# Sheet3.net
KiCad netlist of a schematic drawn in Altium Designer
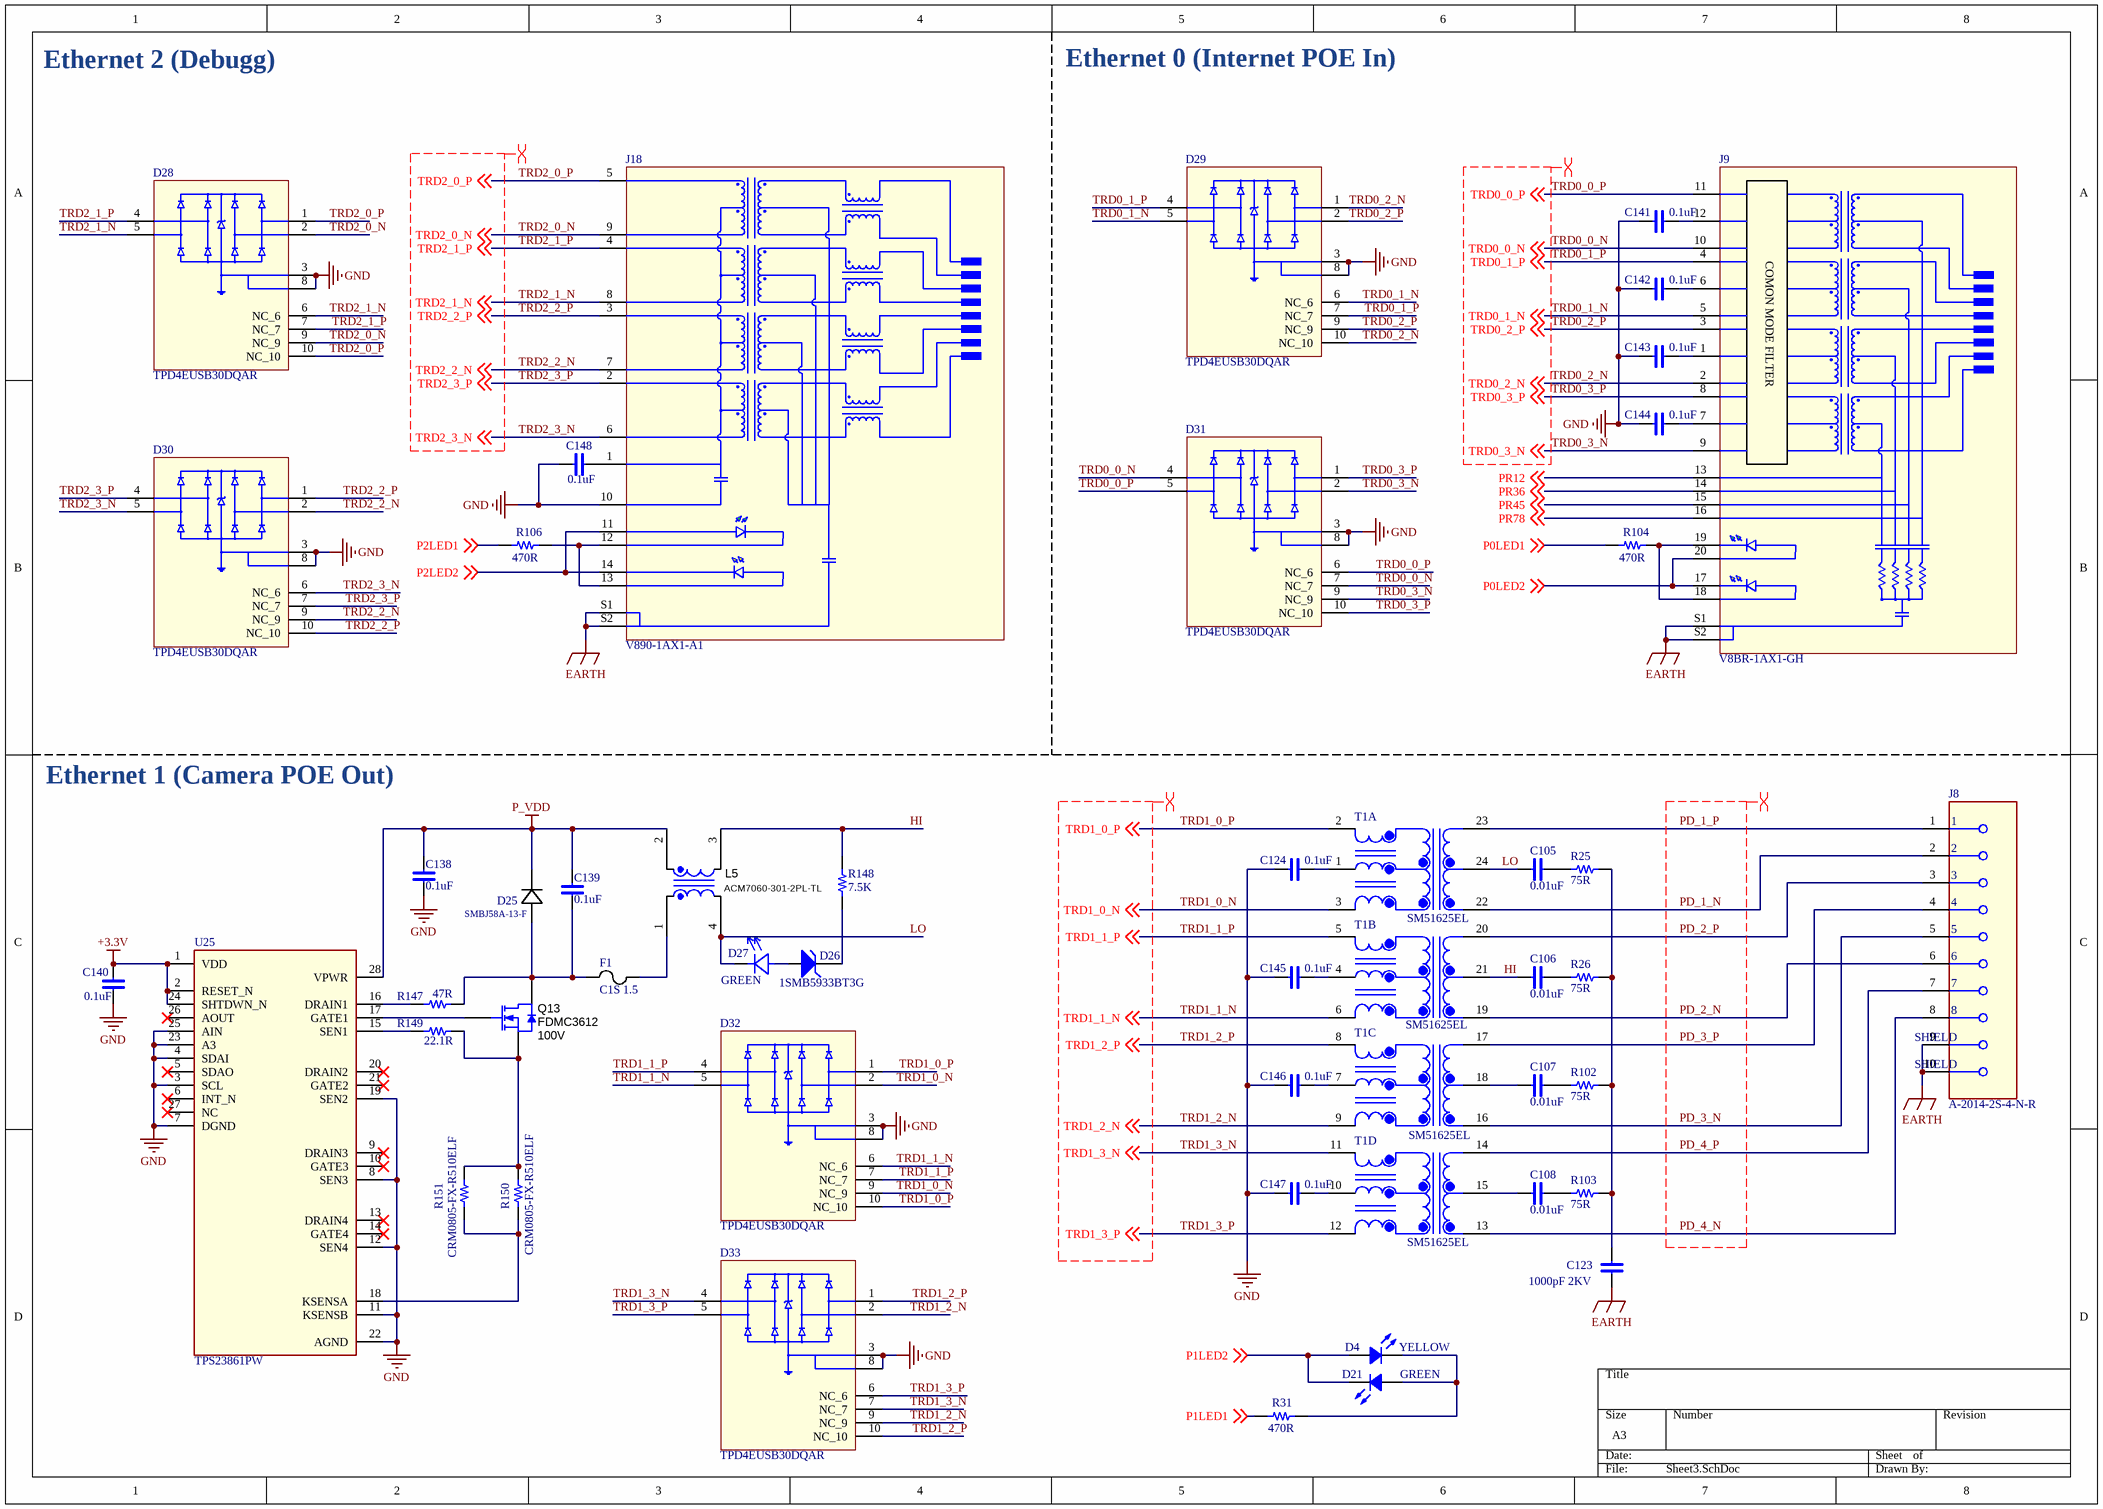
[diagram p0: Sheet3.SchDoc]

(export (version "E")
  (design (tool "Eeschema 10.0.6"))
  (components
    (comp (ref "C105")
      (value "0.01uF")
      (footprint "C-0402/1005")
      (description "CAP CER 0.1UF 50V X7R 0402")
      (fields (field (name "MFR. PART NO.") "UMK105B7104KV-FR"))
      (libsource (lib "") (part "Capacitor-NonPolar_3"))
    )
    (comp (ref "C106")
      (value "0.01uF")
      (footprint "C-0402/1005")
      (description "CAP CER 0.1UF 50V X7R 0402")
      (fields (field (name "MFR. PART NO.") "UMK105B7104KV-FR"))
      (libsource (lib "") (part "Capacitor-NonPolar_3"))
    )
    (comp (ref "C107")
      (value "0.01uF")
      (footprint "C-0402/1005")
      (description "CAP CER 0.1UF 50V X7R 0402")
      (fields (field (name "MFR. PART NO.") "UMK105B7104KV-FR"))
      (libsource (lib "") (part "Capacitor-NonPolar_3"))
    )
    (comp (ref "C108")
      (value "0.01uF")
      (footprint "C-0402/1005")
      (description "CAP CER 0.1UF 50V X7R 0402")
      (fields (field (name "MFR. PART NO.") "UMK105B7104KV-FR"))
      (libsource (lib "") (part "Capacitor-NonPolar_3"))
    )
    (comp (ref "C123")
      (value "1000pF 2KV")
      (footprint "C-0402/1005")
      (description "CAP CER 0.1UF 50V X7R 0402")
      (fields (field (name "MFR. PART NO.") "UMK105B7104KV-FR"))
      (libsource (lib "") (part "Capacitor-NonPolar_2"))
    )
    (comp (ref "C124")
      (value "0.1uF")
      (footprint "C-0402/1005")
      (description "CAP CER 0.1UF 50V X7R 0402")
      (fields (field (name "MFR. PART NO.") "UMK105B7104KV-FR"))
      (libsource (lib "") (part "Capacitor-NonPolar_1"))
    )
    (comp (ref "C138")
      (value "0.1uF")
      (footprint "C-0402/1005")
      (description "CAP CER 0.1UF 50V X7R 0402")
      (fields (field (name "MFR. PART NO.") "UMK105B7104KV-FR"))
      (libsource (lib "Custom_Library") (part "Capacitor-NonPolar"))
    )
    (comp (ref "C139")
      (value "0.1uF")
      (footprint "C-0402/1005")
      (description "CAP CER 0.1UF 50V X7R 0402")
      (fields (field (name "MFR. PART NO.") "UMK105B7104KV-FR"))
      (libsource (lib "Custom_Library") (part "Capacitor-NonPolar"))
    )
    (comp (ref "C140")
      (value "0.1uF")
      (footprint "C-0402/1005")
      (description "CAP CER 0.1UF 50V X7R 0402")
      (fields (field (name "MFR. PART NO.") "UMK105B7104KV-FR"))
      (libsource (lib "Custom_Library") (part "Capacitor-NonPolar"))
    )
    (comp (ref "C141")
      (value "0.1uF")
      (footprint "C-0402/1005")
      (description "CAP CER 0.1UF 50V X7R 0402")
      (fields (field (name "MFR. PART NO.") "UMK105B7104KV-FR"))
      (libsource (lib "") (part "Capacitor-NonPolar_1"))
    )
    (comp (ref "C142")
      (value "0.1uF")
      (footprint "C-0402/1005")
      (description "CAP CER 0.1UF 50V X7R 0402")
      (fields (field (name "MFR. PART NO.") "UMK105B7104KV-FR"))
      (libsource (lib "") (part "Capacitor-NonPolar_1"))
    )
    (comp (ref "C143")
      (value "0.1uF")
      (footprint "C-0402/1005")
      (description "CAP CER 0.1UF 50V X7R 0402")
      (fields (field (name "MFR. PART NO.") "UMK105B7104KV-FR"))
      (libsource (lib "") (part "Capacitor-NonPolar_1"))
    )
    (comp (ref "C144")
      (value "0.1uF")
      (footprint "C-0402/1005")
      (description "CAP CER 0.1UF 50V X7R 0402")
      (fields (field (name "MFR. PART NO.") "UMK105B7104KV-FR"))
      (libsource (lib "") (part "Capacitor-NonPolar_1"))
    )
    (comp (ref "C145")
      (value "0.1uF")
      (footprint "C-0402/1005")
      (description "CAP CER 0.1UF 50V X7R 0402")
      (fields (field (name "MFR. PART NO.") "UMK105B7104KV-FR"))
      (libsource (lib "") (part "Capacitor-NonPolar_1"))
    )
    (comp (ref "C146")
      (value "0.1uF")
      (footprint "C-0402/1005")
      (description "CAP CER 0.1UF 50V X7R 0402")
      (fields (field (name "MFR. PART NO.") "UMK105B7104KV-FR"))
      (libsource (lib "") (part "Capacitor-NonPolar_1"))
    )
    (comp (ref "C147")
      (value "0.1uF")
      (footprint "C-0402/1005")
      (description "CAP CER 0.1UF 50V X7R 0402")
      (fields (field (name "MFR. PART NO.") "UMK105B7104KV-FR"))
      (libsource (lib "") (part "Capacitor-NonPolar_1"))
    )
    (comp (ref "C148")
      (value "0.1uF")
      (footprint "C-0402/1005")
      (description "CAP CER 0.1UF 50V X7R 0402")
      (fields (field (name "MFR. PART NO.") "UMK105B7104KV-FR"))
      (libsource (lib "") (part "Capacitor-NonPolar_1"))
    )
    (comp (ref "D4")
      (value "YELLOW")
      (footprint "LED-0603-RED")
      (description "LED RED CLEAR CHIP SMD R/A")
      (fields (field (name "MFR. PART NO.") "LTST-S270KRKT"))
      (libsource (lib "Diodes") (part "LED SMD"))
    )
    (comp (ref "D21")
      (value "GREEN")
      (footprint "LED-0603-RED")
      (description "LED RED CLEAR CHIP SMD R/A")
      (fields (field (name "MFR. PART NO.") "LTST-S270KRKT"))
      (libsource (lib "Diodes") (part "LED SMD"))
    )
    (comp (ref "D25")
      (value "SMBJ58A-13-F")
      (footprint "CR_SM12CA-13-F_DIO")
      (description "No Description Available")
      (fields (field (name "COPYRIGHT") "Copyright (C) 2023 Ultra Librarian. All rights reserved."))
      (libsource (lib "SMBJ58A-13-F") (part "SMBJ58A-13-F"))
    )
    (comp (ref "D26")
      (value "1SMB5933BT3G")
      (footprint "ONSC-SMB-2-403A-03_H_V")
      (description "3 W Zener Voltage Regulator, 2-Pin SMB, Pb-Free, Tape and Reel")
      (fields (field (name "MANUFACTURER") "On Semiconductor"))
      (libsource (lib "Altium Content Vault") (part "ONSC-K1A2-2"))
    )
    (comp (ref "D27")
      (value "GREEN")
      (footprint "LED-0603-Green")
      (libsource (lib "Custom_Library") (part "Diode-LED"))
    )
    (comp (ref "D28")
      (value "TPD4EUSB30DQAR")
      (footprint "IC_TPD4EUSB30DQAR")
      (description "4-channel ESD solution for SuperSpeed (6 Gbps) USB 3.0 interface 10-USON -40 to 85")
      (libsource (lib "TPD4EUSB30DQAR") (part "TPD4EUSB30DQAR"))
    )
    (comp (ref "D29")
      (value "TPD4EUSB30DQAR")
      (footprint "IC_TPD4EUSB30DQAR")
      (description "4-channel ESD solution for SuperSpeed (6 Gbps) USB 3.0 interface 10-USON -40 to 85")
      (libsource (lib "TPD4EUSB30DQAR") (part "TPD4EUSB30DQAR"))
    )
    (comp (ref "D30")
      (value "TPD4EUSB30DQAR")
      (footprint "IC_TPD4EUSB30DQAR")
      (description "4-channel ESD solution for SuperSpeed (6 Gbps) USB 3.0 interface 10-USON -40 to 85")
      (libsource (lib "TPD4EUSB30DQAR") (part "TPD4EUSB30DQAR"))
    )
    (comp (ref "D31")
      (value "TPD4EUSB30DQAR")
      (footprint "IC_TPD4EUSB30DQAR")
      (description "4-channel ESD solution for SuperSpeed (6 Gbps) USB 3.0 interface 10-USON -40 to 85")
      (libsource (lib "TPD4EUSB30DQAR") (part "TPD4EUSB30DQAR"))
    )
    (comp (ref "D32")
      (value "TPD4EUSB30DQAR")
      (footprint "IC_TPD4EUSB30DQAR")
      (description "4-channel ESD solution for SuperSpeed (6 Gbps) USB 3.0 interface 10-USON -40 to 85")
      (libsource (lib "TPD4EUSB30DQAR") (part "TPD4EUSB30DQAR"))
    )
    (comp (ref "D33")
      (value "TPD4EUSB30DQAR")
      (footprint "IC_TPD4EUSB30DQAR")
      (description "4-channel ESD solution for SuperSpeed (6 Gbps) USB 3.0 interface 10-USON -40 to 85")
      (libsource (lib "TPD4EUSB30DQAR") (part "TPD4EUSB30DQAR"))
    )
    (comp (ref "F1")
      (value "C1S 1.5")
      (footprint "C1_BEL")
      (description "No Description Available")
      (fields (field (name "COPYRIGHT") "Copyright (C) 2023 Ultra Librarian. All rights reserved."))
      (libsource (lib "C1S1P5") (part "C1S 1.5"))
    )
    (comp (ref "J8")
      (value "A-2014-2S-4-N-R")
      (footprint "ASSMANN_A-2014-2S-4-N-R")
      (description "Jack Modular Connector 8p8c (RJ45, Ethernet) Vertical Unshielded")
      (fields (field (name "MP") "A-2014-2-4-N-T-R") (field (name "MF") "ASSMANN WSW Components"))
      (libsource (lib "A-2014-2-4-N-T-R") (part "A-2014-2-4-N-T-R"))
    )
    (comp (ref "J9")
      (value "V8BR-1AX1-GH")
      (footprint "V8BR1AX1GH")
      (description "Conn RJ-45 F 8 POS 1.02mm Solder ST Thru-Hole 20 Terminal 1 Port Tray")
      (fields (field (name "MOUSER PART NUMBER") "530-V8BR-1AX1-GH"))
      (libsource (lib "V8BR-1AX1-GH") (part "V8BR-1AX1-GH"))
    )
    (comp (ref "J18")
      (value "V890-1AX1-A1")
      (footprint "BEL_V890-1AX1-A1")
      (description "MagJack 1000BaseT ¦ 1X1 ¦ G/Y ¦ Vertical ¦ RoHS")
      (fields
        (field (name "MF") "Bel Magnetic Solutions")
        (field (name "DIGI-KEY_PART_NUMBER") "V890-1AX1-A1A-ND")
      )
      (libsource (lib "V890-1AX1-A1") (part "V890-1AX1-A1"))
    )
    (comp (ref "L5")
      (value "ACM7060-301-2PL-TL")
      (footprint "IND_ACM7060_TDK")
      (description "Coupled inductor, 5A, 0.01 ohm, SMD")
      (fields
        (field (name "MANUFACTURER") "TDK")
        (field (name "SYMBOLCREATOR") "a0799628")
        (field (name "PUBLISHER") "Texas Instruments")
      )
      (libsource (lib "Coupled_Inductors") (part "ACM7060-301-2PL-TL"))
    )
    (comp (ref "Q13")
      (value "FDMC3612")
      (footprint "MLP8_3P3X3P3_ONS")
      (description "MOSFET, N-CH, 100V, 3.3A, 3.3x1x3.3mm")
      (fields
        (field (name "MANUFACTURER") "Fairchild Semiconductor")
        (field (name "ALTIUM_VALUE") "100V")
        (field (name "PUBLISHER") "Texas Instruments")
      )
      (libsource (lib "PC22") (part "FDMC3612"))
    )
    (comp (ref "R25")
      (value "75R")
      (footprint "R-0402/1005")
      (description "RES SMD 51 OHM 0.5% 1/16W 0402")
      (fields (field (name "MFR. PART NO.") "ERA-2AED510X"))
      (libsource (lib "Custom_Library") (part "Resistor"))
    )
    (comp (ref "R26")
      (value "75R")
      (footprint "R-0402/1005")
      (description "RES SMD 51 OHM 0.5% 1/16W 0402")
      (fields (field (name "MFR. PART NO.") "ERA-2AED510X"))
      (libsource (lib "Custom_Library") (part "Resistor"))
    )
    (comp (ref "R31")
      (value "470R")
      (footprint "R-0402/1005")
      (description "RES SMD 51 OHM 0.5% 1/16W 0402")
      (fields (field (name "MFR. PART NO.") "ERA-2AED510X"))
      (libsource (lib "Custom_Library") (part "Resistor"))
    )
    (comp (ref "R102")
      (value "75R")
      (footprint "R-0402/1005")
      (description "RES SMD 51 OHM 0.5% 1/16W 0402")
      (fields (field (name "MFR. PART NO.") "ERA-2AED510X"))
      (libsource (lib "Custom_Library") (part "Resistor"))
    )
    (comp (ref "R103")
      (value "75R")
      (footprint "R-0402/1005")
      (description "RES SMD 51 OHM 0.5% 1/16W 0402")
      (fields (field (name "MFR. PART NO.") "ERA-2AED510X"))
      (libsource (lib "Custom_Library") (part "Resistor"))
    )
    (comp (ref "R104")
      (value "470R")
      (footprint "R-0402/1005")
      (description "RES SMD 51 OHM 0.5% 1/16W 0402")
      (fields (field (name "MFR. PART NO.") "ERA-2AED510X"))
      (libsource (lib "Custom_Library") (part "Resistor"))
    )
    (comp (ref "R106")
      (value "470R")
      (footprint "R-0402/1005")
      (description "RES SMD 51 OHM 0.5% 1/16W 0402")
      (fields (field (name "MFR. PART NO.") "ERA-2AED510X"))
      (libsource (lib "Custom_Library") (part "Resistor"))
    )
    (comp (ref "R147")
      (value "47R")
      (footprint "R-0402/1005")
      (description "RES SMD 51 OHM 0.5% 1/16W 0402")
      (fields (field (name "MFR. PART NO.") "ERA-2AED510X"))
      (libsource (lib "Custom_Library") (part "Resistor"))
    )
    (comp (ref "R148")
      (value "7.5K")
      (footprint "R-0805/2012")
      (description "RES SMD 51 OHM 0.5% 1/16W 0402")
      (fields (field (name "MFR. PART NO.") "ERA-2AED510X"))
      (libsource (lib "Custom_Library") (part "Resistor"))
    )
    (comp (ref "R149")
      (value "22.1R")
      (footprint "R-0402/1005")
      (description "RES SMD 51 OHM 0.5% 1/16W 0402")
      (fields (field (name "MFR. PART NO.") "ERA-2AED510X"))
      (libsource (lib "Custom_Library") (part "Resistor"))
    )
    (comp (ref "R150")
      (value "CRM0805-FX-R510ELF")
      (footprint "R-0805/2012")
      (description "RES SMD 51 OHM 0.5% 1/16W 0402")
      (fields (field (name "MFR. PART NO.") "ERA-2AED510X"))
      (libsource (lib "Custom_Library") (part "Resistor"))
    )
    (comp (ref "R151")
      (value "CRM0805-FX-R510ELF")
      (footprint "R-0805/2012")
      (description "RES SMD 51 OHM 0.5% 1/16W 0402")
      (fields (field (name "MFR. PART NO.") "ERA-2AED510X"))
      (libsource (lib "Custom_Library") (part "Resistor"))
    )
    (comp (ref "T1")
      (value "SM51625EL")
      (footprint "XFMR_SM51625EL")
      (description "350ÂµH LAN 10/100/1000 Base-T Pulse Transformer 1CT:1CT Transmitter, 1CT:1CT Receiver Surface Mount")
      (fields (field (name "MF") "Wurth Electronics") (field (name "MP") "7490220122"))
      (libsource (lib "7490220122") (part "7490220122"))
    )
    (comp (ref "U25")
      (value "TPS23861PW")
      (footprint "PW0028A_N")
      (description "No Description Available")
      (fields (field (name "COPYRIGHT") "Copyright (C) 2023 Ultra Librarian. All rights reserved."))
      (libsource (lib "TPS23861PW") (part "TPS23861PW"))
    )
  )
  (nets
    (net (code "1") (name "+3.3V") (class "Default")
      (node (ref "C140") (pin "1") (pinfunction "1_1") (pintype "passive"))
      (node (ref "U25") (pin "1") (pinfunction "VDD_1") (pintype "passive"))
      (node (ref "U25") (pin "2") (pinfunction "RESET_N_2") (pintype "passive"))
      (node (ref "U25") (pin "24") (pinfunction "SHTDWN_N_24") (pintype "passive"))
    )
    (net (code "2") (name "/HI") (class "Default")
      (node (ref "C106") (pin "1") (pinfunction "1_1") (pintype "passive"))
      (node (ref "L5") (pin "3") (pinfunction "3_3") (pintype "passive"))
      (node (ref "R148") (pin "2") (pinfunction "2_2") (pintype "passive"))
      (node (ref "T1") (pin "21") (pinfunction "MCT2_21") (pintype "passive"))
    )
    (net (code "3") (name "/LO") (class "Default")
      (node (ref "C105") (pin "1") (pinfunction "1_1") (pintype "passive"))
      (node (ref "D27") (pin "2") (pinfunction "2_2") (pintype "passive"))
      (node (ref "L5") (pin "4") (pinfunction "4_4") (pintype "passive"))
      (node (ref "T1") (pin "24") (pinfunction "MCT1_24") (pintype "passive"))
    )
    (net (code "4") (name "/PD_1_N") (class "Default")
      (node (ref "J8") (pin "2") (pinfunction "2_2") (pintype "passive"))
      (node (ref "T1") (pin "22") (pinfunction "MX1-_22") (pintype "passive"))
    )
    (net (code "5") (name "/PD_1_P") (class "Default")
      (node (ref "J8") (pin "1") (pinfunction "1_1") (pintype "passive"))
      (node (ref "T1") (pin "23") (pinfunction "MX1+_23") (pintype "passive"))
    )
    (net (code "6") (name "/PD_2_N") (class "Default")
      (node (ref "J8") (pin "6") (pinfunction "6_6") (pintype "passive"))
      (node (ref "T1") (pin "19") (pinfunction "MX2-_19") (pintype "passive"))
    )
    (net (code "7") (name "/PD_2_P") (class "Default")
      (node (ref "J8") (pin "3") (pinfunction "3_3") (pintype "passive"))
      (node (ref "T1") (pin "20") (pinfunction "MX2+_20") (pintype "passive"))
    )
    (net (code "8") (name "/PD_3_N") (class "Default")
      (node (ref "J8") (pin "5") (pinfunction "5_5") (pintype "passive"))
      (node (ref "T1") (pin "16") (pinfunction "MX3-_16") (pintype "passive"))
    )
    (net (code "9") (name "/PD_3_P") (class "Default")
      (node (ref "J8") (pin "4") (pinfunction "4_4") (pintype "passive"))
      (node (ref "T1") (pin "17") (pinfunction "MX3+_17") (pintype "passive"))
    )
    (net (code "10") (name "/PD_4_N") (class "Default")
      (node (ref "J8") (pin "8") (pinfunction "8_8") (pintype "passive"))
      (node (ref "T1") (pin "13") (pinfunction "MX4-_13") (pintype "passive"))
    )
    (net (code "11") (name "/PD_4_P") (class "Default")
      (node (ref "J8") (pin "7") (pinfunction "7_7") (pintype "passive"))
      (node (ref "T1") (pin "14") (pinfunction "MX4+_14") (pintype "passive"))
    )
    (net (code "12") (name "EARTH") (class "Default")
      (node (ref "C123") (pin "2") (pinfunction "2_2") (pintype "passive"))
      (node (ref "J18") (pin "S1") (pinfunction "SHIELD_S1") (pintype "passive"))
      (node (ref "J18") (pin "S2") (pinfunction "SHIELD_S2") (pintype "passive"))
      (node (ref "J8") (pin "10") (pinfunction "MNT_2_10") (pintype "passive"))
      (node (ref "J8") (pin "9") (pinfunction "MNT_1_9") (pintype "passive"))
      (node (ref "J9") (pin "S1") (pinfunction "SHIELD_S1") (pintype "passive"))
      (node (ref "J9") (pin "S2") (pinfunction "SHIELD_S2") (pintype "passive"))
    )
    (net (code "13") (name "GND") (class "Default")
      (node (ref "C124") (pin "1") (pinfunction "1_1") (pintype "passive"))
      (node (ref "C138") (pin "2") (pinfunction "2_2") (pintype "passive"))
      (node (ref "C140") (pin "2") (pinfunction "2_2") (pintype "passive"))
      (node (ref "C141") (pin "1") (pinfunction "1_1") (pintype "passive"))
      (node (ref "C142") (pin "1") (pinfunction "1_1") (pintype "passive"))
      (node (ref "C143") (pin "1") (pinfunction "1_1") (pintype "passive"))
      (node (ref "C144") (pin "1") (pinfunction "1_1") (pintype "passive"))
      (node (ref "C145") (pin "1") (pinfunction "1_1") (pintype "passive"))
      (node (ref "C146") (pin "1") (pinfunction "1_1") (pintype "passive"))
      (node (ref "C147") (pin "1") (pinfunction "1_1") (pintype "passive"))
      (node (ref "C148") (pin "1") (pinfunction "1_1") (pintype "passive"))
      (node (ref "D28") (pin "3") (pinfunction "GND_3_3") (pintype "passive"))
      (node (ref "D28") (pin "8") (pinfunction "GND_8_8") (pintype "passive"))
      (node (ref "D29") (pin "3") (pinfunction "GND_3_3") (pintype "passive"))
      (node (ref "D29") (pin "8") (pinfunction "GND_8_8") (pintype "passive"))
      (node (ref "D30") (pin "3") (pinfunction "GND_3_3") (pintype "passive"))
      (node (ref "D30") (pin "8") (pinfunction "GND_8_8") (pintype "passive"))
      (node (ref "D31") (pin "3") (pinfunction "GND_3_3") (pintype "passive"))
      (node (ref "D31") (pin "8") (pinfunction "GND_8_8") (pintype "passive"))
      (node (ref "D32") (pin "3") (pinfunction "GND_3_3") (pintype "passive"))
      (node (ref "D32") (pin "8") (pinfunction "GND_8_8") (pintype "passive"))
      (node (ref "D33") (pin "3") (pinfunction "GND_3_3") (pintype "passive"))
      (node (ref "D33") (pin "8") (pinfunction "GND_8_8") (pintype "passive"))
      (node (ref "J18") (pin "10") (pinfunction "GND_10") (pintype "power_in"))
      (node (ref "U25") (pin "11") (pinfunction "KSENSB_11") (pintype "passive"))
      (node (ref "U25") (pin "12") (pinfunction "SEN4_12") (pintype "passive"))
      (node (ref "U25") (pin "19") (pinfunction "SEN2_19") (pintype "passive"))
      (node (ref "U25") (pin "22") (pinfunction "AGND_22") (pintype "passive"))
      (node (ref "U25") (pin "23") (pinfunction "A3_23") (pintype "passive"))
      (node (ref "U25") (pin "25") (pinfunction "AIN_25") (pintype "passive"))
      (node (ref "U25") (pin "3") (pinfunction "SCL_3") (pintype "passive"))
      (node (ref "U25") (pin "4") (pinfunction "SDAI_4") (pintype "passive"))
      (node (ref "U25") (pin "7") (pinfunction "DGND_7") (pintype "passive"))
      (node (ref "U25") (pin "8") (pinfunction "SEN3_8") (pintype "passive"))
    )
    (net (code "14") (name "Net-(C105-Pad2)") (class "Default")
      (node (ref "C105") (pin "2") (pinfunction "2_2") (pintype "passive"))
      (node (ref "R25") (pin "1") (pinfunction "1_1") (pintype "passive"))
    )
    (net (code "15") (name "Net-(C106-Pad2)") (class "Default")
      (node (ref "C106") (pin "2") (pinfunction "2_2") (pintype "passive"))
      (node (ref "R26") (pin "1") (pinfunction "1_1") (pintype "passive"))
    )
    (net (code "16") (name "Net-(C107-Pad2)") (class "Default")
      (node (ref "C107") (pin "2") (pinfunction "2_2") (pintype "passive"))
      (node (ref "R102") (pin "1") (pinfunction "1_1") (pintype "passive"))
    )
    (net (code "17") (name "Net-(C108-Pad2)") (class "Default")
      (node (ref "C108") (pin "2") (pinfunction "2_2") (pintype "passive"))
      (node (ref "R103") (pin "1") (pinfunction "1_1") (pintype "passive"))
    )
    (net (code "18") (name "Net-(C123-Pad1)") (class "Default")
      (node (ref "C123") (pin "1") (pinfunction "1_1") (pintype "passive"))
      (node (ref "R102") (pin "2") (pinfunction "2_2") (pintype "passive"))
      (node (ref "R103") (pin "2") (pinfunction "2_2") (pintype "passive"))
      (node (ref "R25") (pin "2") (pinfunction "2_2") (pintype "passive"))
      (node (ref "R26") (pin "2") (pinfunction "2_2") (pintype "passive"))
    )
    (net (code "19") (name "Net-(D21-Pad1)") (class "Default")
      (node (ref "D21") (pin "1") (pinfunction "1_1") (pintype "passive"))
      (node (ref "D4") (pin "2") (pinfunction "2_2") (pintype "passive"))
      (node (ref "R31") (pin "2") (pinfunction "2_2") (pintype "passive"))
    )
    (net (code "20") (name "Net-(D26-A)") (class "Default")
      (node (ref "D26") (pin "2") (pinfunction "A_2") (pintype "passive"))
      (node (ref "D27") (pin "1") (pinfunction "1_1") (pintype "passive"))
    )
    (net (code "21") (name "Net-(D26-K)") (class "Default")
      (node (ref "D26") (pin "1") (pinfunction "K_1") (pintype "passive"))
      (node (ref "R148") (pin "1") (pinfunction "1_1") (pintype "passive"))
    )
    (net (code "22") (name "Net-(F1-Pad2)") (class "Default")
      (node (ref "F1") (pin "2") (pinfunction "2_2") (pintype "passive"))
      (node (ref "L5") (pin "1") (pinfunction "1_1") (pintype "passive"))
    )
    (net (code "23") (name "Net-(J9-Pad18)") (class "Default")
      (node (ref "J9") (pin "18") (pinfunction "18_18") (pintype "passive"))
      (node (ref "J9") (pin "19") (pinfunction "19_19") (pintype "passive"))
      (node (ref "R104") (pin "2") (pinfunction "2_2") (pintype "passive"))
    )
    (net (code "24") (name "Net-(J9-TRCT1)") (class "Default")
      (node (ref "C141") (pin "2") (pinfunction "2_2") (pintype "passive"))
      (node (ref "J9") (pin "12") (pinfunction "TRCT1_12") (pintype "passive"))
    )
    (net (code "25") (name "Net-(J9-TRCT2)") (class "Default")
      (node (ref "C142") (pin "2") (pinfunction "2_2") (pintype "passive"))
      (node (ref "J9") (pin "6") (pinfunction "TRCT2_6") (pintype "passive"))
    )
    (net (code "26") (name "Net-(J9-TRCT3)") (class "Default")
      (node (ref "C143") (pin "2") (pinfunction "2_2") (pintype "passive"))
      (node (ref "J9") (pin "1") (pinfunction "TRCT3_1") (pintype "passive"))
    )
    (net (code "27") (name "Net-(J9-TRCT4)") (class "Default")
      (node (ref "C144") (pin "2") (pinfunction "2_2") (pintype "passive"))
      (node (ref "J9") (pin "7") (pinfunction "TRCT4_7") (pintype "passive"))
    )
    (net (code "28") (name "Net-(J18-Pad12)") (class "Default")
      (node (ref "J18") (pin "12") (pinfunction "12_12") (pintype "passive"))
      (node (ref "J18") (pin "13") (pinfunction "13_13") (pintype "passive"))
      (node (ref "R106") (pin "2") (pinfunction "2_2") (pintype "passive"))
    )
    (net (code "29") (name "Net-(J18-TRDCT1{slash}2{slash}3{slash}4)") (class "Default")
      (node (ref "C148") (pin "2") (pinfunction "2_2") (pintype "passive"))
      (node (ref "J18") (pin "1") (pinfunction "TRDCT1/2/3/4_1") (pintype "passive"))
    )
    (net (code "30") (name "Net-(Q13-D)") (class "Default")
      (node (ref "C139") (pin "2") (pinfunction "2_2") (pintype "passive"))
      (node (ref "D25") (pin "2") (pinfunction "2_2") (pintype "passive"))
      (node (ref "F1") (pin "1") (pinfunction "1_1") (pintype "passive"))
      (node (ref "Q13") (pin "5") (pinfunction "D_5") (pintype "passive"))
      (node (ref "R147") (pin "2") (pinfunction "2_2") (pintype "passive"))
    )
    (net (code "31") (name "Net-(Q13-G)") (class "Default")
      (node (ref "Q13") (pin "4") (pinfunction "G_4") (pintype "passive"))
      (node (ref "U25") (pin "17") (pinfunction "GATE1_17") (pintype "passive"))
    )
    (net (code "32") (name "Net-(Q13-S)") (class "Default")
      (node (ref "Q13") (pin "1") (pinfunction "S_1") (pintype "passive"))
      (node (ref "R149") (pin "2") (pinfunction "2_2") (pintype "passive"))
      (node (ref "R150") (pin "2") (pinfunction "2_2") (pintype "passive"))
      (node (ref "R151") (pin "2") (pinfunction "2_2") (pintype "passive"))
    )
    (net (code "33") (name "Net-(T1A-TCT1)") (class "Default")
      (node (ref "C124") (pin "2") (pinfunction "2_2") (pintype "passive"))
      (node (ref "T1") (pin "1") (pinfunction "TCT1_1") (pintype "passive"))
    )
    (net (code "34") (name "Net-(T1B-TCT2)") (class "Default")
      (node (ref "C145") (pin "2") (pinfunction "2_2") (pintype "passive"))
      (node (ref "T1") (pin "4") (pinfunction "TCT2_4") (pintype "passive"))
    )
    (net (code "35") (name "Net-(T1C-MCT3)") (class "Default")
      (node (ref "C107") (pin "1") (pinfunction "1_1") (pintype "passive"))
      (node (ref "T1") (pin "18") (pinfunction "MCT3_18") (pintype "passive"))
    )
    (net (code "36") (name "Net-(T1C-TCT3)") (class "Default")
      (node (ref "C146") (pin "2") (pinfunction "2_2") (pintype "passive"))
      (node (ref "T1") (pin "7") (pinfunction "TCT3_7") (pintype "passive"))
    )
    (net (code "37") (name "Net-(T1D-MCT4)") (class "Default")
      (node (ref "C108") (pin "1") (pinfunction "1_1") (pintype "passive"))
      (node (ref "T1") (pin "15") (pinfunction "MCT4_15") (pintype "passive"))
    )
    (net (code "38") (name "Net-(T1D-TCT4)") (class "Default")
      (node (ref "C147") (pin "2") (pinfunction "2_2") (pintype "passive"))
      (node (ref "T1") (pin "10") (pinfunction "TCT4_10") (pintype "passive"))
    )
    (net (code "39") (name "Net-(U25-DRAIN1)") (class "Default")
      (node (ref "R147") (pin "1") (pinfunction "1_1") (pintype "passive"))
      (node (ref "U25") (pin "16") (pinfunction "DRAIN1_16") (pintype "passive"))
    )
    (net (code "40") (name "Net-(U25-KSENSA)") (class "Default")
      (node (ref "R150") (pin "1") (pinfunction "1_1") (pintype "passive"))
      (node (ref "R151") (pin "1") (pinfunction "1_1") (pintype "passive"))
      (node (ref "U25") (pin "18") (pinfunction "KSENSA_18") (pintype "passive"))
    )
    (net (code "41") (name "Net-(U25-SEN1)") (class "Default")
      (node (ref "R149") (pin "1") (pinfunction "1_1") (pintype "passive"))
      (node (ref "U25") (pin "15") (pinfunction "SEN1_15") (pintype "passive"))
    )
    (net (code "42") (name "P0LED1") (class "Default")
      (node (ref "R104") (pin "1") (pinfunction "1_1") (pintype "passive"))
    )
    (net (code "43") (name "P0LED2") (class "Default")
      (node (ref "J9") (pin "17") (pinfunction "17_17") (pintype "passive"))
      (node (ref "J9") (pin "20") (pinfunction "20_20") (pintype "passive"))
    )
    (net (code "44") (name "P1LED1") (class "Default")
      (node (ref "R31") (pin "1") (pinfunction "1_1") (pintype "passive"))
    )
    (net (code "45") (name "P1LED2") (class "Default")
      (node (ref "D21") (pin "2") (pinfunction "2_2") (pintype "passive"))
      (node (ref "D4") (pin "1") (pinfunction "1_1") (pintype "passive"))
    )
    (net (code "46") (name "P2LED1") (class "Default")
      (node (ref "R106") (pin "1") (pinfunction "1_1") (pintype "passive"))
    )
    (net (code "47") (name "P2LED2") (class "Default")
      (node (ref "J18") (pin "11") (pinfunction "11_11") (pintype "passive"))
      (node (ref "J18") (pin "14") (pinfunction "14_14") (pintype "passive"))
    )
    (net (code "48") (name "PR12") (class "Default")
      (node (ref "J9") (pin "13") (pinfunction "VC12_13") (pintype "passive"))
    )
    (net (code "49") (name "PR36") (class "Default")
      (node (ref "J9") (pin "14") (pinfunction "VC36_14") (pintype "passive"))
    )
    (net (code "50") (name "PR45") (class "Default")
      (node (ref "J9") (pin "15") (pinfunction "VC45_15") (pintype "passive"))
    )
    (net (code "51") (name "PR78") (class "Default")
      (node (ref "J9") (pin "16") (pinfunction "VC78_16") (pintype "passive"))
    )
    (net (code "52") (name "P_VDD") (class "Default")
      (node (ref "C138") (pin "1") (pinfunction "1_1") (pintype "passive"))
      (node (ref "C139") (pin "1") (pinfunction "1_1") (pintype "passive"))
      (node (ref "D25") (pin "1") (pinfunction "1_1") (pintype "passive"))
      (node (ref "L5") (pin "2") (pinfunction "2_2") (pintype "passive"))
      (node (ref "U25") (pin "28") (pinfunction "VPWR_28") (pintype "passive"))
    )
    (net (code "53") (name "TRD0_0_N") (class "Default")
      (node (ref "D31") (pin "4") (pinfunction "D2+_4") (pintype "passive"))
      (node (ref "D31") (pin "7") (pinfunction "NC_7_7") (pintype "passive"))
      (node (ref "J9") (pin "10") (pinfunction "TRD1-_10") (pintype "passive"))
    )
    (net (code "54") (name "TRD0_0_P") (class "Default")
      (node (ref "D31") (pin "5") (pinfunction "D2-_5") (pintype "passive"))
      (node (ref "D31") (pin "6") (pinfunction "NC_6_6") (pintype "passive"))
      (node (ref "J9") (pin "11") (pinfunction "TRD1+_11") (pintype "passive"))
    )
    (net (code "55") (name "TRD0_1_N") (class "Default")
      (node (ref "D29") (pin "5") (pinfunction "D2-_5") (pintype "passive"))
      (node (ref "D29") (pin "6") (pinfunction "NC_6_6") (pintype "passive"))
      (node (ref "J9") (pin "5") (pinfunction "TRD2-_5") (pintype "passive"))
    )
    (net (code "56") (name "TRD0_1_P") (class "Default")
      (node (ref "D29") (pin "4") (pinfunction "D2+_4") (pintype "passive"))
      (node (ref "D29") (pin "7") (pinfunction "NC_7_7") (pintype "passive"))
      (node (ref "J9") (pin "4") (pinfunction "TRD2+_4") (pintype "passive"))
    )
    (net (code "57") (name "TRD0_2_N") (class "Default")
      (node (ref "D29") (pin "1") (pinfunction "D1+_1") (pintype "passive"))
      (node (ref "D29") (pin "10") (pinfunction "NC_10_10") (pintype "passive"))
      (node (ref "J9") (pin "2") (pinfunction "TRD3-_2") (pintype "passive"))
    )
    (net (code "58") (name "TRD0_2_P") (class "Default")
      (node (ref "D29") (pin "2") (pinfunction "D1-_2") (pintype "passive"))
      (node (ref "D29") (pin "9") (pinfunction "NC_9_9") (pintype "passive"))
      (node (ref "J9") (pin "3") (pinfunction "TRD3+_3") (pintype "passive"))
    )
    (net (code "59") (name "TRD0_3_N") (class "Default")
      (node (ref "D31") (pin "2") (pinfunction "D1-_2") (pintype "passive"))
      (node (ref "D31") (pin "9") (pinfunction "NC_9_9") (pintype "passive"))
      (node (ref "J9") (pin "9") (pinfunction "TRD4-_9") (pintype "passive"))
    )
    (net (code "60") (name "TRD0_3_P") (class "Default")
      (node (ref "D31") (pin "1") (pinfunction "D1+_1") (pintype "passive"))
      (node (ref "D31") (pin "10") (pinfunction "NC_10_10") (pintype "passive"))
      (node (ref "J9") (pin "8") (pinfunction "TRD4+_8") (pintype "passive"))
    )
    (net (code "61") (name "TRD1_0_N") (class "Default")
      (node (ref "D32") (pin "2") (pinfunction "D1-_2") (pintype "passive"))
      (node (ref "D32") (pin "9") (pinfunction "NC_9_9") (pintype "passive"))
      (node (ref "T1") (pin "3") (pinfunction "TD1-_3") (pintype "passive"))
    )
    (net (code "62") (name "TRD1_0_P") (class "Default")
      (node (ref "D32") (pin "1") (pinfunction "D1+_1") (pintype "passive"))
      (node (ref "D32") (pin "10") (pinfunction "NC_10_10") (pintype "passive"))
      (node (ref "T1") (pin "2") (pinfunction "TD1+_2") (pintype "passive"))
    )
    (net (code "63") (name "TRD1_1_N") (class "Default")
      (node (ref "D32") (pin "5") (pinfunction "D2-_5") (pintype "passive"))
      (node (ref "D32") (pin "6") (pinfunction "NC_6_6") (pintype "passive"))
      (node (ref "T1") (pin "6") (pinfunction "TD2-_6") (pintype "passive"))
    )
    (net (code "64") (name "TRD1_1_P") (class "Default")
      (node (ref "D32") (pin "4") (pinfunction "D2+_4") (pintype "passive"))
      (node (ref "D32") (pin "7") (pinfunction "NC_7_7") (pintype "passive"))
      (node (ref "T1") (pin "5") (pinfunction "TD2+_5") (pintype "passive"))
    )
    (net (code "65") (name "TRD1_2_N") (class "Default")
      (node (ref "D33") (pin "2") (pinfunction "D1-_2") (pintype "passive"))
      (node (ref "D33") (pin "9") (pinfunction "NC_9_9") (pintype "passive"))
      (node (ref "T1") (pin "9") (pinfunction "TD3-_9") (pintype "passive"))
    )
    (net (code "66") (name "TRD1_2_P") (class "Default")
      (node (ref "D33") (pin "1") (pinfunction "D1+_1") (pintype "passive"))
      (node (ref "D33") (pin "10") (pinfunction "NC_10_10") (pintype "passive"))
      (node (ref "T1") (pin "8") (pinfunction "TD3+_8") (pintype "passive"))
    )
    (net (code "67") (name "TRD1_3_N") (class "Default")
      (node (ref "D33") (pin "4") (pinfunction "D2+_4") (pintype "passive"))
      (node (ref "D33") (pin "7") (pinfunction "NC_7_7") (pintype "passive"))
      (node (ref "T1") (pin "11") (pinfunction "TD4+_11") (pintype "passive"))
    )
    (net (code "68") (name "TRD1_3_P") (class "Default")
      (node (ref "D33") (pin "5") (pinfunction "D2-_5") (pintype "passive"))
      (node (ref "D33") (pin "6") (pinfunction "NC_6_6") (pintype "passive"))
      (node (ref "T1") (pin "12") (pinfunction "TD4-_12") (pintype "passive"))
    )
    (net (code "69") (name "TRD2_0_N") (class "Default")
      (node (ref "D28") (pin "2") (pinfunction "D1-_2") (pintype "passive"))
      (node (ref "D28") (pin "9") (pinfunction "NC_9_9") (pintype "passive"))
      (node (ref "J18") (pin "9") (pinfunction "TRD1-_9") (pintype "passive"))
    )
    (net (code "70") (name "TRD2_0_P") (class "Default")
      (node (ref "D28") (pin "1") (pinfunction "D1+_1") (pintype "passive"))
      (node (ref "D28") (pin "10") (pinfunction "NC_10_10") (pintype "passive"))
      (node (ref "J18") (pin "5") (pinfunction "TRD1+_5") (pintype "passive"))
    )
    (net (code "71") (name "TRD2_1_N") (class "Default")
      (node (ref "D28") (pin "5") (pinfunction "D2-_5") (pintype "passive"))
      (node (ref "D28") (pin "6") (pinfunction "NC_6_6") (pintype "passive"))
      (node (ref "J18") (pin "8") (pinfunction "TRD2-_8") (pintype "passive"))
    )
    (net (code "72") (name "TRD2_1_P") (class "Default")
      (node (ref "D28") (pin "4") (pinfunction "D2+_4") (pintype "passive"))
      (node (ref "D28") (pin "7") (pinfunction "NC_7_7") (pintype "passive"))
      (node (ref "J18") (pin "4") (pinfunction "TRD2+_4") (pintype "passive"))
    )
    (net (code "73") (name "TRD2_2_N") (class "Default")
      (node (ref "D30") (pin "2") (pinfunction "D1-_2") (pintype "passive"))
      (node (ref "D30") (pin "9") (pinfunction "NC_9_9") (pintype "passive"))
      (node (ref "J18") (pin "7") (pinfunction "TRD3-_7") (pintype "passive"))
    )
    (net (code "74") (name "TRD2_2_P") (class "Default")
      (node (ref "D30") (pin "1") (pinfunction "D1+_1") (pintype "passive"))
      (node (ref "D30") (pin "10") (pinfunction "NC_10_10") (pintype "passive"))
      (node (ref "J18") (pin "3") (pinfunction "TRD3+_3") (pintype "passive"))
    )
    (net (code "75") (name "TRD2_3_N") (class "Default")
      (node (ref "D30") (pin "5") (pinfunction "D2-_5") (pintype "passive"))
      (node (ref "D30") (pin "6") (pinfunction "NC_6_6") (pintype "passive"))
      (node (ref "J18") (pin "6") (pinfunction "TRD4-_6") (pintype "passive"))
    )
    (net (code "76") (name "TRD2_3_P") (class "Default")
      (node (ref "D30") (pin "4") (pinfunction "D2+_4") (pintype "passive"))
      (node (ref "D30") (pin "7") (pinfunction "NC_7_7") (pintype "passive"))
      (node (ref "J18") (pin "2") (pinfunction "TRD4+_2") (pintype "passive"))
    )
    (net (code "77") (name "unconnected-(U25-AOUT-Pad26)") (class "Default")
      (node (ref "U25") (pin "26") (pinfunction "AOUT_26") (pintype "passive+no_connect"))
    )
    (net (code "78") (name "unconnected-(U25-DRAIN2-Pad20)") (class "Default")
      (node (ref "U25") (pin "20") (pinfunction "DRAIN2_20") (pintype "passive+no_connect"))
    )
    (net (code "79") (name "unconnected-(U25-DRAIN3-Pad9)") (class "Default")
      (node (ref "U25") (pin "9") (pinfunction "DRAIN3_9") (pintype "passive+no_connect"))
    )
    (net (code "80") (name "unconnected-(U25-DRAIN4-Pad13)") (class "Default")
      (node (ref "U25") (pin "13") (pinfunction "DRAIN4_13") (pintype "passive+no_connect"))
    )
    (net (code "81") (name "unconnected-(U25-GATE2-Pad21)") (class "Default")
      (node (ref "U25") (pin "21") (pinfunction "GATE2_21") (pintype "passive+no_connect"))
    )
    (net (code "82") (name "unconnected-(U25-GATE3-Pad10)") (class "Default")
      (node (ref "U25") (pin "10") (pinfunction "GATE3_10") (pintype "passive+no_connect"))
    )
    (net (code "83") (name "unconnected-(U25-GATE4-Pad14)") (class "Default")
      (node (ref "U25") (pin "14") (pinfunction "GATE4_14") (pintype "passive+no_connect"))
    )
    (net (code "84") (name "unconnected-(U25-INT_N-Pad6)") (class "Default")
      (node (ref "U25") (pin "6") (pinfunction "INT_N_6") (pintype "passive+no_connect"))
    )
    (net (code "85") (name "unconnected-(U25-NC-Pad27)") (class "Default")
      (node (ref "U25") (pin "27") (pinfunction "NC_27") (pintype "passive+no_connect"))
    )
    (net (code "86") (name "unconnected-(U25-SDAO-Pad5)") (class "Default")
      (node (ref "U25") (pin "5") (pinfunction "SDAO_5") (pintype "passive+no_connect"))
    )
  )
)
